# TMK-EURO-0_1_1.net
KiCad netlist of a schematic drawn in EAGLE
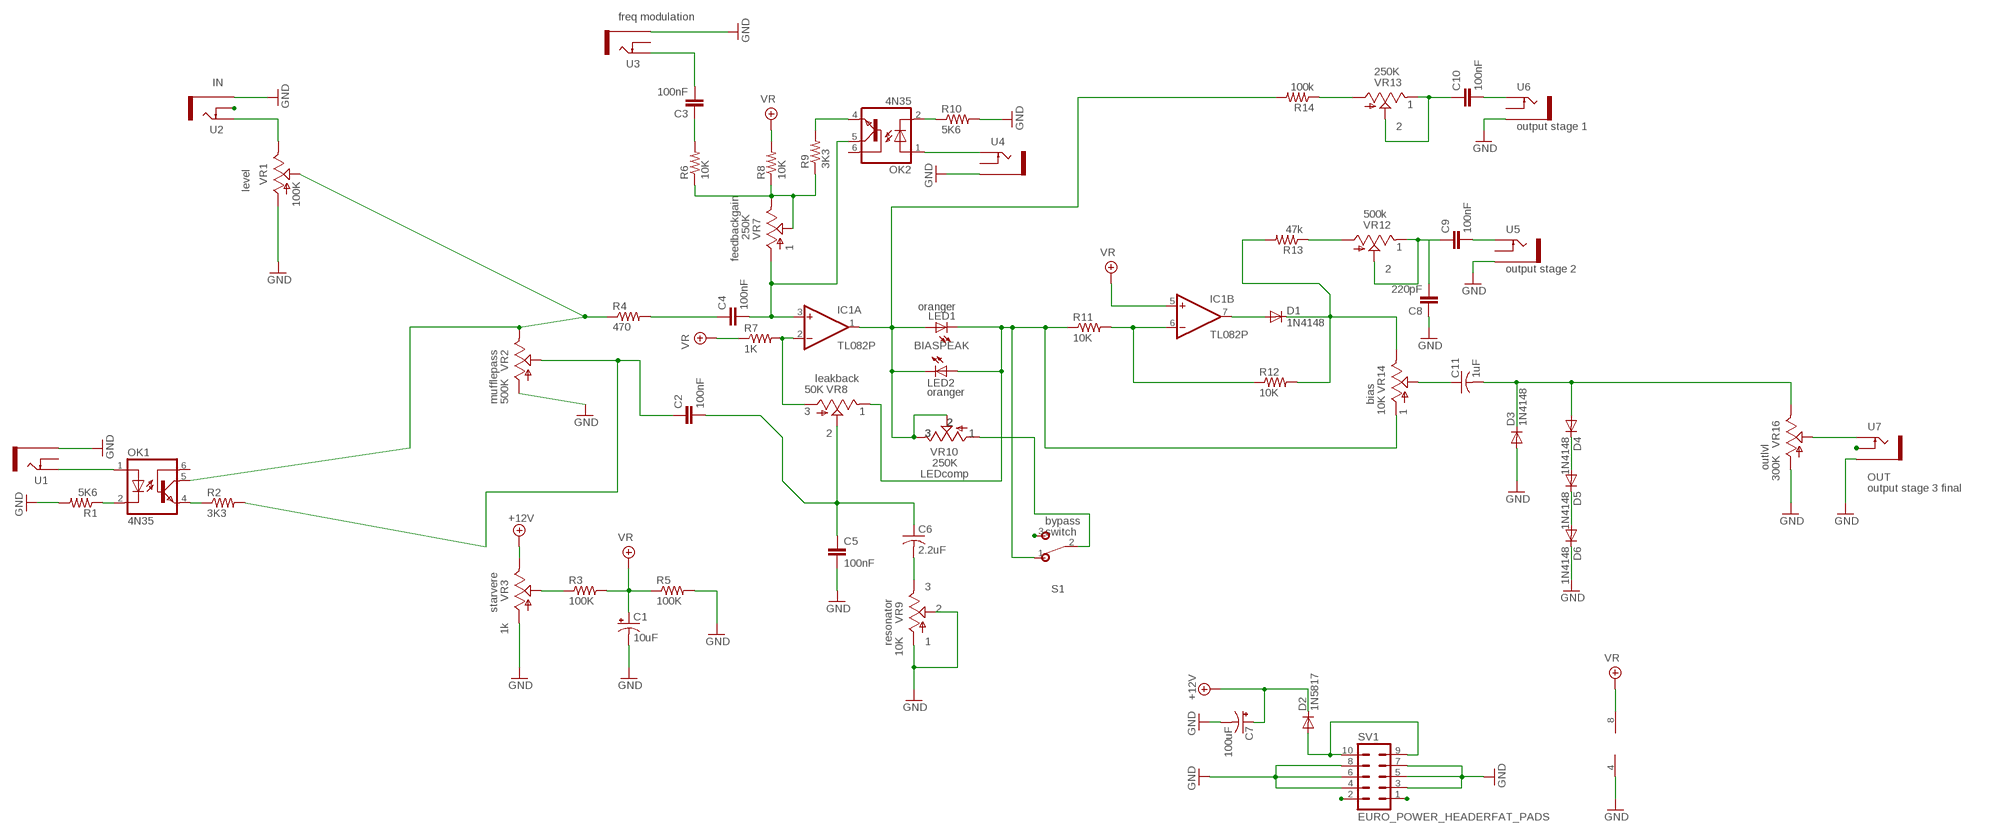
[diagram p0: schematic, sheet 1]

(export (version "E")
  (design (tool "Eeschema 10.0.6"))
  (components
    (comp (ref "C1")
      (value "10uF")
      (footprint "eagle-import:E2-5")
      (libsource (lib "eagle-import") (part "CPOL-USE2-5"))
    )
    (comp (ref "C2")
      (value "100nF")
      (footprint "eagle-import:C050-035X075")
      (libsource (lib "eagle-import") (part "C-EU050-035X075"))
    )
    (comp (ref "C3")
      (value "100nF")
      (footprint "eagle-import:C050-035X075")
      (libsource (lib "eagle-import") (part "C-EU050-035X075"))
    )
    (comp (ref "C4")
      (value "100nF")
      (footprint "eagle-import:C050-035X075")
      (libsource (lib "eagle-import") (part "C-EU050-035X075"))
    )
    (comp (ref "C5")
      (value "100nF")
      (footprint "eagle-import:C050-035X075")
      (libsource (lib "eagle-import") (part "C-EU050-035X075"))
    )
    (comp (ref "C6")
      (value "2.2uF")
      (footprint "eagle-import:C050-030X075")
      (libsource (lib "eagle-import") (part "C-US050-030X075"))
    )
    (comp (ref "C7")
      (value "100uF")
      (footprint "eagle-import:080_035")
      (libsource (lib "eagle-import") (part "080"))
    )
    (comp (ref "C8")
      (value "220pF")
      (footprint "eagle-import:C050-035X075")
      (libsource (lib "eagle-import") (part "C-EU050-035X075"))
    )
    (comp (ref "C9")
      (value "100nF")
      (footprint "eagle-import:C050-035X075")
      (libsource (lib "eagle-import") (part "C-EU050-035X075"))
    )
    (comp (ref "C10")
      (value "100nF")
      (footprint "eagle-import:C050-035X075")
      (libsource (lib "eagle-import") (part "C-EU050-035X075"))
    )
    (comp (ref "C11")
      (value "1uF")
      (footprint "eagle-import:C050-075X075")
      (libsource (lib "eagle-import") (part "C-US050-075X075"))
    )
    (comp (ref "D1")
      (value "1N4148")
      (footprint "eagle-import:DO35-7")
      (libsource (lib "eagle-import") (part "SMALL_DIODEDO35-7"))
    )
    (comp (ref "D2")
      (value "1N5817")
      (footprint "eagle-import:DO35-7")
      (libsource (lib "eagle-import") (part "SMALL_DIODEDO35-7"))
    )
    (comp (ref "D3")
      (value "1N4148")
      (footprint "eagle-import:DO35-7")
      (libsource (lib "eagle-import") (part "SMALL_DIODEDO35-7"))
    )
    (comp (ref "D4")
      (value "1N4148")
      (footprint "eagle-import:DO35-7")
      (libsource (lib "eagle-import") (part "SMALL_DIODEDO35-7"))
    )
    (comp (ref "D5")
      (value "1N4148")
      (footprint "eagle-import:DO35-7")
      (libsource (lib "eagle-import") (part "SMALL_DIODEDO35-7"))
    )
    (comp (ref "D6")
      (value "1N4148")
      (footprint "eagle-import:DO35-7")
      (libsource (lib "eagle-import") (part "SMALL_DIODEDO35-7"))
    )
    (comp (ref "IC1")
      (value "TL082P")
      (footprint "eagle-import:DIL08")
      (libsource (lib "eagle-import") (part "TL082P"))
    )
    (comp (ref "LED1")
      (value "oranger")
      (footprint "eagle-import:LED3MM")
      (libsource (lib "eagle-import") (part "LED3MM"))
    )
    (comp (ref "LED2")
      (value "oranger")
      (footprint "eagle-import:LED3MM")
      (libsource (lib "eagle-import") (part "LED3MM"))
    )
    (comp (ref "OK1")
      (value "4N35")
      (footprint "eagle-import:DIL06")
      (fields (field (name "MF") "FAIRCHILD SEMICONDUCTOR"))
      (libsource (lib "eagle-import") (part "4N35"))
    )
    (comp (ref "OK2")
      (value "4N35")
      (footprint "eagle-import:DIL06")
      (fields (field (name "MF") "FAIRCHILD SEMICONDUCTOR"))
      (libsource (lib "eagle-import") (part "4N35"))
    )
    (comp (ref "R1")
      (value "5K6")
      (footprint "eagle-import:0207_7")
      (libsource (lib "eagle-import") (part "R-US_0207/7"))
    )
    (comp (ref "R2")
      (value "3K3")
      (footprint "eagle-import:0207_7")
      (libsource (lib "eagle-import") (part "R-US_0207/7"))
    )
    (comp (ref "R3")
      (value "100K")
      (footprint "eagle-import:0207_7")
      (libsource (lib "eagle-import") (part "R-US_0207/7"))
    )
    (comp (ref "R4")
      (value "470")
      (footprint "eagle-import:0207_7")
      (libsource (lib "eagle-import") (part "R-US_0207/7"))
    )
    (comp (ref "R5")
      (value "100K")
      (footprint "eagle-import:0207_7")
      (libsource (lib "eagle-import") (part "R-US_0207/7"))
    )
    (comp (ref "R6")
      (value "10K")
      (footprint "eagle-import:0207_7")
      (libsource (lib "eagle-import") (part "R-US_0207/7"))
    )
    (comp (ref "R7")
      (value "1K")
      (footprint "eagle-import:0207_7")
      (libsource (lib "eagle-import") (part "R-US_0207/7"))
    )
    (comp (ref "R8")
      (value "10K")
      (footprint "eagle-import:0207_7")
      (libsource (lib "eagle-import") (part "R-US_0207/7"))
    )
    (comp (ref "R9")
      (value "3K3")
      (footprint "eagle-import:0207_7")
      (libsource (lib "eagle-import") (part "R-US_0207/7"))
    )
    (comp (ref "R10")
      (value "5K6")
      (footprint "eagle-import:0207_7")
      (libsource (lib "eagle-import") (part "R-US_0207/7"))
    )
    (comp (ref "R11")
      (value "10K")
      (footprint "eagle-import:0207_7")
      (libsource (lib "eagle-import") (part "R-US_0207/7"))
    )
    (comp (ref "R12")
      (value "10K")
      (footprint "eagle-import:0207_7")
      (libsource (lib "eagle-import") (part "R-US_0207/7"))
    )
    (comp (ref "R13")
      (value "47k")
      (footprint "eagle-import:0207_7")
      (libsource (lib "eagle-import") (part "R-US_0207/7"))
    )
    (comp (ref "R14")
      (value "100k")
      (footprint "eagle-import:0207_7")
      (libsource (lib "eagle-import") (part "R-US_0207/7"))
    )
    (comp (ref "S1")
      (value "SPDTPADS")
      (footprint "eagle-import:SPDT")
      (libsource (lib "eagle-import") (part "SPDTPADS"))
    )
    (comp (ref "SV1")
      (value "EURO_POWER_HEADERFAT_PADS")
      (footprint "eagle-import:EURO_PWR_HEADER_FAT")
      (libsource (lib "eagle-import") (part "EURO_POWER_HEADERFAT_PADS"))
    )
    (comp (ref "U1")
      (value "IN")
      (footprint "eagle-import:THONKICONN")
      (libsource (lib "eagle-import") (part "THONKICONNOLD"))
    )
    (comp (ref "U2")
      (value "IN")
      (footprint "eagle-import:THONKICONN")
      (libsource (lib "eagle-import") (part "THONKICONNOLD"))
    )
    (comp (ref "U3")
      (value "IN")
      (footprint "eagle-import:THONKICONN")
      (libsource (lib "eagle-import") (part "THONKICONNOLD"))
    )
    (comp (ref "U4")
      (value "IN")
      (footprint "eagle-import:THONKICONN")
      (libsource (lib "eagle-import") (part "THONKICONNOLD"))
    )
    (comp (ref "U5")
      (value "IN")
      (footprint "eagle-import:THONKICONN")
      (libsource (lib "eagle-import") (part "THONKICONNOLD"))
    )
    (comp (ref "U6")
      (value "IN")
      (footprint "eagle-import:THONKICONN")
      (libsource (lib "eagle-import") (part "THONKICONNOLD"))
    )
    (comp (ref "U7")
      (value "THONKICONNOLD")
      (footprint "eagle-import:THONKICONN")
      (libsource (lib "eagle-import") (part "THONKICONNOLD"))
    )
    (comp (ref "VR1")
      (value "100K")
      (footprint "eagle-import:9MM_SNAP-IN_POT")
      (libsource (lib "eagle-import") (part "9MM_SNAP-IN_POT_"))
    )
    (comp (ref "VR2")
      (value "500K")
      (footprint "eagle-import:9MM_SNAP-IN_POT")
      (libsource (lib "eagle-import") (part "9MM_SNAP-IN_POT_"))
    )
    (comp (ref "VR3")
      (value "1k")
      (footprint "eagle-import:9MM_SNAP-IN_POT")
      (libsource (lib "eagle-import") (part "9MM_SNAP-IN_POT_"))
    )
    (comp (ref "VR7")
      (value "250K")
      (footprint "eagle-import:9MM_SNAP-IN_POT")
      (libsource (lib "eagle-import") (part "9MM_SNAP-IN_POT_"))
    )
    (comp (ref "VR8")
      (value "50K")
      (footprint "eagle-import:9MM_SNAP-IN_POT")
      (libsource (lib "eagle-import") (part "9MM_SNAP-IN_POT_"))
    )
    (comp (ref "VR9")
      (value "10K")
      (footprint "eagle-import:9MM_SNAP-IN_POT")
      (libsource (lib "eagle-import") (part "9MM_SNAP-IN_POT_"))
    )
    (comp (ref "VR10")
      (value "250K")
      (footprint "eagle-import:9MM_SNAP-IN_POT")
      (libsource (lib "eagle-import") (part "9MM_SNAP-IN_POT_"))
    )
    (comp (ref "VR12")
      (value "500k")
      (footprint "eagle-import:9MM_SNAP-IN_POT")
      (libsource (lib "eagle-import") (part "9MM_SNAP-IN_POT_"))
    )
    (comp (ref "VR13")
      (value "250K")
      (footprint "eagle-import:9MM_SNAP-IN_POT")
      (libsource (lib "eagle-import") (part "9MM_SNAP-IN_POT_"))
    )
    (comp (ref "VR14")
      (value "10K")
      (footprint "eagle-import:9MM_SNAP-IN_POT")
      (libsource (lib "eagle-import") (part "9MM_SNAP-IN_POT_"))
    )
    (comp (ref "VR16")
      (value "300K")
      (footprint "eagle-import:9MM_SNAP-IN_POT")
      (libsource (lib "eagle-import") (part "9MM_SNAP-IN_POT_"))
    )
  )
  (nets
    (net (code "1") (name "+12V") (class "Default")
      (node (ref "C7") (pin "+") (pinfunction "+_+") (pintype "passive"))
      (node (ref "D2") (pin "C") (pinfunction "C_C") (pintype "passive"))
      (node (ref "VR3") (pin "3") (pinfunction "E_3") (pintype "passive"))
    )
    (net (code "2") (name "GND") (class "Default")
      (node (ref "C1") (pin "-") (pinfunction "-_-") (pintype "passive"))
      (node (ref "C5") (pin "2") (pinfunction "2_2") (pintype "passive"))
      (node (ref "C7") (pin "-") (pinfunction "-_-") (pintype "passive"))
      (node (ref "C8") (pin "1") (pinfunction "1_1") (pintype "passive"))
      (node (ref "D3") (pin "A") (pinfunction "A_A") (pintype "passive"))
      (node (ref "D6") (pin "C") (pinfunction "C_C") (pintype "passive"))
      (node (ref "IC1") (pin "4") (pinfunction "V-_4") (pintype "power_in"))
      (node (ref "R1") (pin "2") (pinfunction "2_2") (pintype "passive"))
      (node (ref "R10") (pin "2") (pinfunction "2_2") (pintype "passive"))
      (node (ref "R5") (pin "2") (pinfunction "2_2") (pintype "passive"))
      (node (ref "SV1") (pin "3") (pinfunction "3_3") (pintype "passive"))
      (node (ref "SV1") (pin "4") (pinfunction "4_4") (pintype "passive"))
      (node (ref "SV1") (pin "5") (pinfunction "5_5") (pintype "passive"))
      (node (ref "SV1") (pin "6") (pinfunction "6_6") (pintype "passive"))
      (node (ref "SV1") (pin "7") (pinfunction "7_7") (pintype "passive"))
      (node (ref "SV1") (pin "8") (pinfunction "8_8") (pintype "passive"))
      (node (ref "U1") (pin "P$1_SLEEVE") (pinfunction "SLEEVE_P$1_SLEEVE") (pintype "passive"))
      (node (ref "U2") (pin "P$1_SLEEVE") (pinfunction "SLEEVE_P$1_SLEEVE") (pintype "passive"))
      (node (ref "U3") (pin "P$1_SLEEVE") (pinfunction "SLEEVE_P$1_SLEEVE") (pintype "passive"))
      (node (ref "U4") (pin "P$1_SLEEVE") (pinfunction "SLEEVE_P$1_SLEEVE") (pintype "passive"))
      (node (ref "U5") (pin "P$1_SLEEVE") (pinfunction "SLEEVE_P$1_SLEEVE") (pintype "passive"))
      (node (ref "U6") (pin "P$1_SLEEVE") (pinfunction "SLEEVE_P$1_SLEEVE") (pintype "passive"))
      (node (ref "U7") (pin "P$1_SLEEVE") (pinfunction "SLEEVE_P$1_SLEEVE") (pintype "passive"))
      (node (ref "VR1") (pin "1") (pinfunction "A_1") (pintype "passive"))
      (node (ref "VR16") (pin "1") (pinfunction "A_1") (pintype "passive"))
      (node (ref "VR2") (pin "1") (pinfunction "A_1") (pintype "passive"))
      (node (ref "VR3") (pin "1") (pinfunction "A_1") (pintype "passive"))
      (node (ref "VR9") (pin "1") (pinfunction "A_1") (pintype "passive"))
      (node (ref "VR9") (pin "2") (pinfunction "S_2") (pintype "passive"))
    )
    (net (code "3") (name "Net-(C3-Pad1)") (class "Default")
      (node (ref "C3") (pin "1") (pinfunction "1_1") (pintype "passive"))
      (node (ref "R6") (pin "2") (pinfunction "2_2") (pintype "passive"))
    )
    (net (code "4") (name "Net-(C4-Pad1)") (class "Default")
      (node (ref "C4") (pin "1") (pinfunction "1_1") (pintype "passive"))
      (node (ref "R4") (pin "2") (pinfunction "2_2") (pintype "passive"))
    )
    (net (code "5") (name "Net-(D2-PadA)") (class "Default")
      (node (ref "D2") (pin "A") (pinfunction "A_A") (pintype "passive"))
      (node (ref "SV1") (pin "10") (pinfunction "10_10") (pintype "passive"))
      (node (ref "SV1") (pin "9") (pinfunction "9_9") (pintype "passive"))
    )
    (net (code "6") (name "Net-(D4-PadC)") (class "Default")
      (node (ref "D4") (pin "C") (pinfunction "C_C") (pintype "passive"))
      (node (ref "D5") (pin "A") (pinfunction "A_A") (pintype "passive"))
    )
    (net (code "7") (name "Net-(D5-PadC)") (class "Default")
      (node (ref "D5") (pin "C") (pinfunction "C_C") (pintype "passive"))
      (node (ref "D6") (pin "A") (pinfunction "A_A") (pintype "passive"))
    )
    (net (code "8") (name "Net-(IC1A-+IN)") (class "Default")
      (node (ref "C4") (pin "2") (pinfunction "2_2") (pintype "passive"))
      (node (ref "IC1") (pin "3") (pinfunction "+IN_3") (pintype "input"))
      (node (ref "OK2") (pin "5") (pinfunction "COL_5") (pintype "passive"))
      (node (ref "VR7") (pin "1") (pinfunction "A_1") (pintype "passive"))
    )
    (net (code "9") (name "Net-(IC1A--IN)") (class "Default")
      (node (ref "IC1") (pin "2") (pinfunction "-IN_2") (pintype "input"))
      (node (ref "R7") (pin "2") (pinfunction "2_2") (pintype "passive"))
      (node (ref "VR8") (pin "1") (pinfunction "A_1") (pintype "passive"))
    )
    (net (code "10") (name "Net-(IC1A-OUT)") (class "Default")
      (node (ref "IC1") (pin "1") (pinfunction "OUT_1") (pintype "output"))
      (node (ref "LED1") (pin "A") (pinfunction "A_A") (pintype "passive"))
      (node (ref "LED2") (pin "K") (pinfunction "C_K") (pintype "passive"))
      (node (ref "R14") (pin "2") (pinfunction "2_2") (pintype "passive"))
      (node (ref "VR10") (pin "2") (pinfunction "S_2") (pintype "passive"))
      (node (ref "VR10") (pin "3") (pinfunction "E_3") (pintype "passive"))
    )
    (net (code "11") (name "Net-(IC1B--IN)") (class "Default")
      (node (ref "IC1") (pin "6") (pinfunction "-IN_6") (pintype "input"))
      (node (ref "R11") (pin "2") (pinfunction "2_2") (pintype "passive"))
      (node (ref "R12") (pin "1") (pinfunction "1_1") (pintype "passive"))
    )
    (net (code "12") (name "Net-(IC1B-OUT)") (class "Default")
      (node (ref "D1") (pin "A") (pinfunction "A_A") (pintype "passive"))
      (node (ref "IC1") (pin "7") (pinfunction "OUT_7") (pintype "output"))
    )
    (net (code "13") (name "Net-(LED1-C)") (class "Default")
      (node (ref "LED1") (pin "K") (pinfunction "C_K") (pintype "passive"))
      (node (ref "LED2") (pin "A") (pinfunction "A_A") (pintype "passive"))
      (node (ref "R11") (pin "1") (pinfunction "1_1") (pintype "passive"))
      (node (ref "S1") (pin "1") (pinfunction "O_1") (pintype "passive"))
      (node (ref "VR14") (pin "1") (pinfunction "A_1") (pintype "passive"))
      (node (ref "VR8") (pin "3") (pinfunction "E_3") (pintype "passive"))
    )
    (net (code "14") (name "Net-(OK1-A)") (class "Default")
      (node (ref "OK1") (pin "1") (pinfunction "A_1") (pintype "passive"))
      (node (ref "U1") (pin "P$3_TIP") (pinfunction "TIP_P$3_TIP") (pintype "passive"))
    )
    (net (code "15") (name "Net-(OK1-C)") (class "Default")
      (node (ref "OK1") (pin "2") (pinfunction "C_2") (pintype "passive"))
      (node (ref "R1") (pin "1") (pinfunction "1_1") (pintype "passive"))
    )
    (net (code "16") (name "Net-(OK1-COL)") (class "Default")
      (node (ref "OK1") (pin "5") (pinfunction "COL_5") (pintype "passive"))
      (node (ref "R4") (pin "1") (pinfunction "1_1") (pintype "passive"))
      (node (ref "VR1") (pin "2") (pinfunction "S_2") (pintype "passive"))
      (node (ref "VR2") (pin "3") (pinfunction "E_3") (pintype "passive"))
    )
    (net (code "17") (name "Net-(OK1-EMI)") (class "Default")
      (node (ref "OK1") (pin "4") (pinfunction "EMI_4") (pintype "passive"))
      (node (ref "R2") (pin "1") (pinfunction "1_1") (pintype "passive"))
    )
    (net (code "18") (name "Net-(OK2-A)") (class "Default")
      (node (ref "OK2") (pin "1") (pinfunction "A_1") (pintype "passive"))
      (node (ref "U4") (pin "P$3_TIP") (pinfunction "TIP_P$3_TIP") (pintype "passive"))
    )
    (net (code "19") (name "Net-(OK2-C)") (class "Default")
      (node (ref "OK2") (pin "2") (pinfunction "C_2") (pintype "passive"))
      (node (ref "R10") (pin "1") (pinfunction "1_1") (pintype "passive"))
    )
    (net (code "20") (name "Net-(OK2-EMI)") (class "Default")
      (node (ref "OK2") (pin "4") (pinfunction "EMI_4") (pintype "passive"))
      (node (ref "R9") (pin "2") (pinfunction "2_2") (pintype "passive"))
    )
    (net (code "21") (name "Net-(S1-P)") (class "Default")
      (node (ref "S1") (pin "2") (pinfunction "P_2") (pintype "passive"))
      (node (ref "VR10") (pin "1") (pinfunction "A_1") (pintype "passive"))
    )
    (net (code "22") (name "Net-(U2-TIP)") (class "Default")
      (node (ref "U2") (pin "P$3_TIP") (pinfunction "TIP_P$3_TIP") (pintype "passive"))
      (node (ref "VR1") (pin "3") (pinfunction "E_3") (pintype "passive"))
    )
    (net (code "23") (name "Net-(U3-TIP)") (class "Default")
      (node (ref "C3") (pin "2") (pinfunction "2_2") (pintype "passive"))
      (node (ref "U3") (pin "P$3_TIP") (pinfunction "TIP_P$3_TIP") (pintype "passive"))
    )
    (net (code "24") (name "Net-(U5-TIP)") (class "Default")
      (node (ref "C9") (pin "2") (pinfunction "2_2") (pintype "passive"))
      (node (ref "U5") (pin "P$3_TIP") (pinfunction "TIP_P$3_TIP") (pintype "passive"))
    )
    (net (code "25") (name "Net-(U6-TIP)") (class "Default")
      (node (ref "C10") (pin "2") (pinfunction "2_2") (pintype "passive"))
      (node (ref "U6") (pin "P$3_TIP") (pinfunction "TIP_P$3_TIP") (pintype "passive"))
    )
    (net (code "26") (name "Net-(U7-TIP)") (class "Default")
      (node (ref "U7") (pin "P$3_TIP") (pinfunction "TIP_P$3_TIP") (pintype "passive"))
      (node (ref "VR16") (pin "2") (pinfunction "S_2") (pintype "passive"))
    )
    (net (code "27") (name "Net-(VR2-S)") (class "Default")
      (node (ref "C2") (pin "1") (pinfunction "1_1") (pintype "passive"))
      (node (ref "R2") (pin "2") (pinfunction "2_2") (pintype "passive"))
      (node (ref "VR2") (pin "2") (pinfunction "S_2") (pintype "passive"))
    )
    (net (code "28") (name "Net-(VR3-S)") (class "Default")
      (node (ref "R3") (pin "1") (pinfunction "1_1") (pintype "passive"))
      (node (ref "VR3") (pin "2") (pinfunction "S_2") (pintype "passive"))
    )
    (net (code "29") (name "Net-(VR7-E)") (class "Default")
      (node (ref "R6") (pin "1") (pinfunction "1_1") (pintype "passive"))
      (node (ref "R8") (pin "1") (pinfunction "1_1") (pintype "passive"))
      (node (ref "R9") (pin "1") (pinfunction "1_1") (pintype "passive"))
      (node (ref "VR7") (pin "2") (pinfunction "S_2") (pintype "passive"))
      (node (ref "VR7") (pin "3") (pinfunction "E_3") (pintype "passive"))
    )
    (net (code "30") (name "Net-(VR8-S)") (class "Default")
      (node (ref "C2") (pin "2") (pinfunction "2_2") (pintype "passive"))
      (node (ref "C5") (pin "1") (pinfunction "1_1") (pintype "passive"))
      (node (ref "C6") (pin "1") (pinfunction "1_1") (pintype "passive"))
      (node (ref "VR8") (pin "2") (pinfunction "S_2") (pintype "passive"))
    )
    (net (code "31") (name "Net-(VR9-E)") (class "Default")
      (node (ref "C6") (pin "2") (pinfunction "2_2") (pintype "passive"))
      (node (ref "VR9") (pin "3") (pinfunction "E_3") (pintype "passive"))
    )
    (net (code "32") (name "Net-(VR12-A)") (class "Default")
      (node (ref "R13") (pin "1") (pinfunction "1_1") (pintype "passive"))
      (node (ref "VR12") (pin "1") (pinfunction "A_1") (pintype "passive"))
    )
    (net (code "33") (name "Net-(VR12-E)") (class "Default")
      (node (ref "C8") (pin "2") (pinfunction "2_2") (pintype "passive"))
      (node (ref "C9") (pin "1") (pinfunction "1_1") (pintype "passive"))
      (node (ref "VR12") (pin "2") (pinfunction "S_2") (pintype "passive"))
      (node (ref "VR12") (pin "3") (pinfunction "E_3") (pintype "passive"))
    )
    (net (code "34") (name "Net-(VR13-A)") (class "Default")
      (node (ref "R14") (pin "1") (pinfunction "1_1") (pintype "passive"))
      (node (ref "VR13") (pin "1") (pinfunction "A_1") (pintype "passive"))
    )
    (net (code "35") (name "Net-(VR13-E)") (class "Default")
      (node (ref "C10") (pin "1") (pinfunction "1_1") (pintype "passive"))
      (node (ref "VR13") (pin "2") (pinfunction "S_2") (pintype "passive"))
      (node (ref "VR13") (pin "3") (pinfunction "E_3") (pintype "passive"))
    )
    (net (code "36") (name "Net-(VR14-E)") (class "Default")
      (node (ref "D1") (pin "C") (pinfunction "C_C") (pintype "passive"))
      (node (ref "R12") (pin "2") (pinfunction "2_2") (pintype "passive"))
      (node (ref "R13") (pin "2") (pinfunction "2_2") (pintype "passive"))
      (node (ref "VR14") (pin "3") (pinfunction "E_3") (pintype "passive"))
    )
    (net (code "37") (name "Net-(VR14-S)") (class "Default")
      (node (ref "C11") (pin "1") (pinfunction "1_1") (pintype "passive"))
      (node (ref "VR14") (pin "2") (pinfunction "S_2") (pintype "passive"))
    )
    (net (code "38") (name "Net-(VR16-E)") (class "Default")
      (node (ref "C11") (pin "2") (pinfunction "2_2") (pintype "passive"))
      (node (ref "D3") (pin "C") (pinfunction "C_C") (pintype "passive"))
      (node (ref "D4") (pin "A") (pinfunction "A_A") (pintype "passive"))
      (node (ref "VR16") (pin "3") (pinfunction "E_3") (pintype "passive"))
    )
    (net (code "39") (name "VR") (class "Default")
      (node (ref "C1") (pin "+") (pinfunction "+_+") (pintype "passive"))
      (node (ref "IC1") (pin "5") (pinfunction "+IN_5") (pintype "input"))
      (node (ref "IC1") (pin "8") (pinfunction "V+_8") (pintype "power_in"))
      (node (ref "R3") (pin "2") (pinfunction "2_2") (pintype "passive"))
      (node (ref "R5") (pin "1") (pinfunction "1_1") (pintype "passive"))
      (node (ref "R7") (pin "1") (pinfunction "1_1") (pintype "passive"))
      (node (ref "R8") (pin "2") (pinfunction "2_2") (pintype "passive"))
    )
    (net (code "40") (name "unconnected-(OK1-BAS-Pad6)") (class "Default")
      (node (ref "OK1") (pin "6") (pinfunction "BAS_6") (pintype "passive"))
    )
    (net (code "41") (name "unconnected-(OK2-BAS-Pad6)") (class "Default")
      (node (ref "OK2") (pin "6") (pinfunction "BAS_6") (pintype "passive"))
    )
    (net (code "42") (name "unconnected-(S1-S-Pad3)") (class "Default")
      (node (ref "S1") (pin "3") (pinfunction "S_3") (pintype "passive"))
    )
    (net (code "43") (name "unconnected-(SV1-Pad1)") (class "Default")
      (node (ref "SV1") (pin "1") (pinfunction "1_1") (pintype "passive"))
    )
    (net (code "44") (name "unconnected-(SV1-Pad2)") (class "Default")
      (node (ref "SV1") (pin "2") (pinfunction "2_2") (pintype "passive"))
    )
    (net (code "45") (name "unconnected-(U1-SWITCH-PadP$2_SWITCH)") (class "Default")
      (node (ref "U1") (pin "P$2_SWITCH") (pinfunction "SWITCH_P$2_SWITCH") (pintype "passive"))
    )
    (net (code "46") (name "unconnected-(U2-SWITCH-PadP$2_SWITCH)") (class "Default")
      (node (ref "U2") (pin "P$2_SWITCH") (pinfunction "SWITCH_P$2_SWITCH") (pintype "passive"))
    )
    (net (code "47") (name "unconnected-(U3-SWITCH-PadP$2_SWITCH)") (class "Default")
      (node (ref "U3") (pin "P$2_SWITCH") (pinfunction "SWITCH_P$2_SWITCH") (pintype "passive"))
    )
    (net (code "48") (name "unconnected-(U4-SWITCH-PadP$2_SWITCH)") (class "Default")
      (node (ref "U4") (pin "P$2_SWITCH") (pinfunction "SWITCH_P$2_SWITCH") (pintype "passive"))
    )
    (net (code "49") (name "unconnected-(U5-SWITCH-PadP$2_SWITCH)") (class "Default")
      (node (ref "U5") (pin "P$2_SWITCH") (pinfunction "SWITCH_P$2_SWITCH") (pintype "passive"))
    )
    (net (code "50") (name "unconnected-(U6-SWITCH-PadP$2_SWITCH)") (class "Default")
      (node (ref "U6") (pin "P$2_SWITCH") (pinfunction "SWITCH_P$2_SWITCH") (pintype "passive"))
    )
    (net (code "51") (name "unconnected-(U7-SWITCH-PadP$2_SWITCH)") (class "Default")
      (node (ref "U7") (pin "P$2_SWITCH") (pinfunction "SWITCH_P$2_SWITCH") (pintype "passive"))
    )
  )
)
